# Ethylene_Sensor_Rev3.net
KiCad netlist of a schematic drawn in Altium Designer
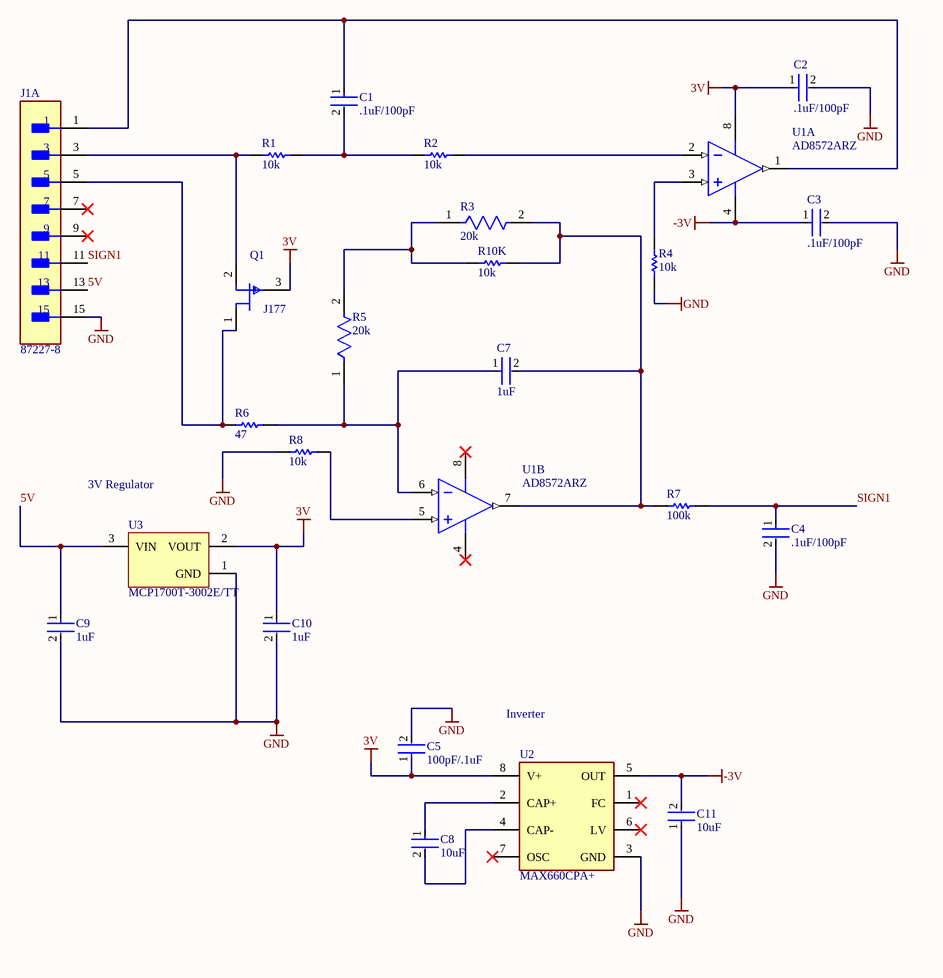
[diagram p0: Ethylene Sensor Rev3.SchDoc]

(export (version "E")
  (design (tool "Eeschema 10.0.6"))
  (components
    (comp (ref "C1")
      (value ".1uF/100pF")
      (footprint "FP-RCE0K1-MFG")
      (description "Cap Ceramic 100pF 100V C0G ±5% Radial 5mm +125°C Automotive Bulk")
      (fields (field (name "TOLERANCE") "5%"))
      (libsource (lib "Altium Content Vault") (part "b4654b650e69147ec39a6b967a45e02"))
    )
    (comp (ref "C2")
      (value ".1uF/100pF")
      (footprint "FP-RCE0K1-MFG")
      (description "Cap Ceramic 100pF 100V C0G ±5% Radial 5mm +125°C Automotive Bulk")
      (fields (field (name "TOLERANCE") "5%"))
      (libsource (lib "Altium Content Vault") (part "b4654b650e69147ec39a6b967a45e02"))
    )
    (comp (ref "C3")
      (value ".1uF/100pF")
      (footprint "FP-RCE0K1-MFG")
      (description "Cap Ceramic 100pF 100V C0G ±5% Radial 5mm +125°C Automotive Bulk")
      (fields (field (name "TOLERANCE") "5%"))
      (libsource (lib "Altium Content Vault") (part "b4654b650e69147ec39a6b967a45e02"))
    )
    (comp (ref "C4")
      (value ".1uF/100pF")
      (footprint "FP-RCE0K1-MFG")
      (description "Cap Ceramic 100pF 100V C0G ±5% Radial 5mm +125°C Automotive Bulk")
      (fields (field (name "TOLERANCE") "5%"))
      (libsource (lib "Altium Content Vault") (part "b4654b650e69147ec39a6b967a45e02"))
    )
    (comp (ref "C5")
      (value "100pF/.1uF")
      (footprint "FP-RCE0DB-MFG")
      (description "Cap Ceramic 100pF 100V C0G ±5% Radial 2.5mm +125°C Ammo Pack")
      (fields (field (name "TOLERANCE") "5%"))
      (libsource (lib "Altium Content Vault") (part "b4654b650e69147ec39a6b967a45e02"))
    )
    (comp (ref "C7")
      (value "1uF")
      (footprint "FP-K105Z20Y5VF5TL2-MFG")
      (description "CAP CER 1UF 50V Y5V RADIAL")
      (fields
        (field (name "TOLERANCE") "-20+80%")
        (field (name "OCTOPART") "https://octopart.com/k105z20y5vf5tl2-vishay-39475252")
      )
      (libsource (lib "Altium Content Vault") (part "11868f565c42a9108669ba33697ecf6"))
    )
    (comp (ref "C8")
      (value "10uF")
      (footprint "FP-RCE3M1-MFG")
      (description "Cap Ceramic 10uF 25V X7R ±10% Radial 5mm +125°C Automotive Ammo Pack")
      (fields (field (name "TOLERANCE") "10%"))
      (libsource (lib "Altium Content Vault") (part "02cd4be3c70576c341d710602a673aa"))
    )
    (comp (ref "C9")
      (value "1uF")
      (footprint "FP-K105Z20Y5VF5TL2-MFG")
      (description "CAP CER 1UF 50V Y5V RADIAL")
      (fields
        (field (name "TOLERANCE") "-20+80%")
        (field (name "OCTOPART") "https://octopart.com/k105z20y5vf5tl2-vishay-39475252")
      )
      (libsource (lib "Altium Content Vault") (part "11868f565c42a9108669ba33697ecf6"))
    )
    (comp (ref "C10")
      (value "1uF")
      (footprint "FP-K105Z20Y5VF5TL2-MFG")
      (description "CAP CER 1UF 50V Y5V RADIAL")
      (fields
        (field (name "TOLERANCE") "-20+80%")
        (field (name "OCTOPART") "https://octopart.com/k105z20y5vf5tl2-vishay-39475252")
      )
      (libsource (lib "Altium Content Vault") (part "11868f565c42a9108669ba33697ecf6"))
    )
    (comp (ref "C11")
      (value "10uF")
      (footprint "FP-RCE3M1-MFG")
      (description "Cap Ceramic 10uF 25V X7R ±10% Radial 5mm +125°C Automotive Ammo Pack")
      (fields (field (name "TOLERANCE") "10%"))
      (libsource (lib "Altium Content Vault") (part "02cd4be3c70576c341d710602a673aa"))
    )
    (comp (ref "J1")
      (value "87227-8")
      (footprint "FP-87227-8-MFG")
      (description "CONN HEADER VERT 16POS 2.54MM")
      (fields
        (field (name "MANUFACTURER") "TE Connectivity")
        (field (name "OCTOPART") "https://octopart.com/87227-8-te+connectivity-39407754")
      )
      (libsource (lib "Altium Content Vault") (part "4b6d22b45e2f925f038cba5d936fbcc"))
    )
    (comp (ref "Q1")
      (value "J177")
      (footprint "FP-318-08-IPC_C")
      (description "JFET P-CH 30V 0.225W SOT23")
      (libsource (lib "Altium Content Vault") (part "f35b6042eff1b6cb0a0a26375b7670e"))
    )
    (comp (ref "R1")
      (value "10k")
      (footprint "OMTE-RES7X2.5-2")
      (fields
        (field (name "TOLERANCE") "±5%")
        (field (name "PARTNUMBER") "OD103JE")
        (field (name "MANUFACTURER") "Ohmite")
      )
      (libsource (lib "Altium Content Vault") (part "RES-2"))
    )
    (comp (ref "R2")
      (value "10k")
      (footprint "OMTE-RES7X2.5-2")
      (fields
        (field (name "TOLERANCE") "±5%")
        (field (name "PARTNUMBER") "OD103JE")
        (field (name "MANUFACTURER") "Ohmite")
      )
      (libsource (lib "Altium Content Vault") (part "RES-2"))
    )
    (comp (ref "R3")
      (value "20k")
      (footprint "FP-S102K-MFG")
      (description "RES 20K OHM 0.6W 0.01% RADIAL")
      (fields (field (name "TOLERANCE") "0.01%"))
      (libsource (lib "Altium Content Vault") (part "1029c3af85768c4190bb7ad29bc67b5"))
    )
    (comp (ref "R4")
      (value "10k")
      (footprint "OMTE-RES7X2.5-2")
      (fields
        (field (name "TOLERANCE") "±5%")
        (field (name "PARTNUMBER") "OD103JE")
        (field (name "MANUFACTURER") "Ohmite")
      )
      (libsource (lib "Altium Content Vault") (part "RES-2"))
    )
    (comp (ref "R5")
      (value "20k")
      (footprint "FP-S102K-MFG")
      (description "RES 20K OHM 0.6W 0.01% RADIAL")
      (fields (field (name "TOLERANCE") "0.01%"))
      (libsource (lib "Altium Content Vault") (part "1029c3af85768c4190bb7ad29bc67b5"))
    )
    (comp (ref "R6")
      (value "47")
      (footprint "RESC1609X50X30LL10T20")
      (fields (field (name "MANUFACTURER") "Vishay Dale") (field (name "PART NUMBER") "CRCW060347R0FKEA"))
      (libsource (lib "Altium Content Vault") (part "RES"))
    )
    (comp (ref "R7")
      (value "100k")
      (footprint "RESA60-630X240")
      (description "Axial Resistor, 100 KOhm, +/- 1%, 0.25 W, -55 to 155 degC, 2-Pin THD, RoHS, Bulk")
      (fields (field (name "TOLERANCE") "1%"))
      (libsource (lib "Altium Content Vault") (part "RES-2"))
    )
    (comp (ref "R8")
      (value "10k")
      (footprint "OMTE-RES7X2.5-2")
      (fields
        (field (name "TOLERANCE") "±5%")
        (field (name "PARTNUMBER") "OD103JE")
        (field (name "MANUFACTURER") "Ohmite")
      )
      (libsource (lib "Altium Content Vault") (part "RES-2"))
    )
    (comp (ref "R10K")
      (value "10k")
      (footprint "OMTE-RES7X2.5-2")
      (fields
        (field (name "TOLERANCE") "±5%")
        (field (name "PARTNUMBER") "OD103JE")
        (field (name "MANUFACTURER") "Ohmite")
      )
      (libsource (lib "Altium Content Vault") (part "RES-2"))
    )
    (comp (ref "U1")
      (value "AD8572ARZ")
      (footprint "ADI-R-8_L")
      (fields (field (name "MANUFACTURER") "Analog Devices") (field (name "GENERIC PART NUMBER") "AD8572"))
      (libsource (lib "Altium Content Vault") (part "ADI-OP29X-R-8"))
    )
    (comp (ref "U2")
      (value "MAX660CPA+")
      (footprint "FP-P8-2-MFG")
      (description "IC REG CHARG PUMP INV 100MA 8DIP")
      (fields
        (field (name "OCTOPART") "https://octopart.com/max660cpa%2B-maxim+integrated-39427913")
        (field (name "MANUFACTURER") "Maxim Integrated")
      )
      (libsource (lib "Altium Content Vault") (part "cb4f88f8f8861f0afe4fdc40404f196"))
    )
    (comp (ref "U3")
      (value "MCP1700T-3002E/TT")
      (footprint "SOT-23-TT3_L")
      (description "Low Quiescent Current LDO, 3-Pin SOT-23, Extended Temperature, Tape and Reel")
      (libsource (lib "Altium Content Vault") (part "PM-LINEREG-MCP1700-IL3"))
    )
  )
  (nets
    (net (code "1") (name "-3V") (class "Default")
      (node (ref "C11") (pin "2") (pinfunction "2_2") (pintype "passive"))
      (node (ref "C3") (pin "1") (pinfunction "1_1") (pintype "passive"))
      (node (ref "U1") (pin "4") (pinfunction "-V_4") (pintype "power_in"))
      (node (ref "U2") (pin "5") (pinfunction "OUT_5") (pintype "power_in"))
    )
    (net (code "2") (name "/5V") (class "Default")
      (node (ref "C9") (pin "1") (pinfunction "1_1") (pintype "passive"))
      (node (ref "J1") (pin "13") (pinfunction "13_13") (pintype "passive"))
      (node (ref "U3") (pin "3") (pinfunction "VIN_3") (pintype "power_in"))
    )
    (net (code "3") (name "/SIGN1") (class "Default")
      (node (ref "C4") (pin "1") (pinfunction "1_1") (pintype "passive"))
      (node (ref "J1") (pin "11") (pinfunction "11_11") (pintype "passive"))
      (node (ref "R7") (pin "2") (pinfunction "2_2") (pintype "passive"))
    )
    (net (code "4") (name "3V") (class "Default")
      (node (ref "C10") (pin "1") (pinfunction "1_1") (pintype "passive"))
      (node (ref "C2") (pin "1") (pinfunction "1_1") (pintype "passive"))
      (node (ref "C5") (pin "1") (pinfunction "1_1") (pintype "passive"))
      (node (ref "Q1") (pin "3") (pinfunction "G_3") (pintype "passive"))
      (node (ref "U1") (pin "8") (pinfunction "+V_8") (pintype "power_in"))
      (node (ref "U2") (pin "8") (pinfunction "V+_8") (pintype "power_in"))
      (node (ref "U3") (pin "2") (pinfunction "VOUT_2") (pintype "power_in"))
    )
    (net (code "5") (name "GND") (class "Default")
      (node (ref "C10") (pin "2") (pinfunction "2_2") (pintype "passive"))
      (node (ref "C11") (pin "1") (pinfunction "1_1") (pintype "passive"))
      (node (ref "C2") (pin "2") (pinfunction "2_2") (pintype "passive"))
      (node (ref "C3") (pin "2") (pinfunction "2_2") (pintype "passive"))
      (node (ref "C4") (pin "2") (pinfunction "2_2") (pintype "passive"))
      (node (ref "C5") (pin "2") (pinfunction "2_2") (pintype "passive"))
      (node (ref "C9") (pin "2") (pinfunction "2_2") (pintype "passive"))
      (node (ref "J1") (pin "15") (pinfunction "15_15") (pintype "passive"))
      (node (ref "R4") (pin "1") (pinfunction "1_1") (pintype "passive"))
      (node (ref "R8") (pin "1") (pinfunction "1_1") (pintype "passive"))
      (node (ref "U2") (pin "3") (pinfunction "GND_3") (pintype "power_in"))
      (node (ref "U3") (pin "1") (pinfunction "GND_1") (pintype "power_in"))
    )
    (net (code "6") (name "Net-(C1-Pad2)") (class "Default")
      (node (ref "C1") (pin "2") (pinfunction "2_2") (pintype "passive"))
      (node (ref "R1") (pin "2") (pinfunction "2_2") (pintype "passive"))
      (node (ref "R2") (pin "1") (pinfunction "1_1") (pintype "passive"))
    )
    (net (code "7") (name "Net-(Q1-D)") (class "Default")
      (node (ref "J1") (pin "5") (pinfunction "5_5") (pintype "passive"))
      (node (ref "Q1") (pin "1") (pinfunction "D_1") (pintype "passive"))
      (node (ref "R6") (pin "1") (pinfunction "1_1") (pintype "passive"))
    )
    (net (code "8") (name "Net-(Q1-S)") (class "Default")
      (node (ref "J1") (pin "3") (pinfunction "3_3") (pintype "passive"))
      (node (ref "Q1") (pin "2") (pinfunction "S_2") (pintype "passive"))
      (node (ref "R1") (pin "1") (pinfunction "1_1") (pintype "passive"))
    )
    (net (code "9") (name "Net-(R10K-Pad1)") (class "Default")
      (node (ref "R10K") (pin "1") (pinfunction "1_1") (pintype "passive"))
      (node (ref "R3") (pin "1") (pinfunction "1_1") (pintype "passive"))
      (node (ref "R5") (pin "2") (pinfunction "2_2") (pintype "passive"))
    )
    (net (code "10") (name "Net-(U1A-+IN_A)") (class "Default")
      (node (ref "R4") (pin "2") (pinfunction "2_2") (pintype "passive"))
      (node (ref "U1") (pin "3") (pinfunction "+IN_A_3") (pintype "input"))
    )
    (net (code "11") (name "Net-(U1A--IN_A)") (class "Default")
      (node (ref "R2") (pin "2") (pinfunction "2_2") (pintype "passive"))
      (node (ref "U1") (pin "2") (pinfunction "-IN_A_2") (pintype "input"))
    )
    (net (code "12") (name "Net-(U1A-OUT_A)") (class "Default")
      (node (ref "C1") (pin "1") (pinfunction "1_1") (pintype "passive"))
      (node (ref "J1") (pin "1") (pinfunction "1_1") (pintype "passive"))
      (node (ref "U1") (pin "1") (pinfunction "OUT_A_1") (pintype "output"))
    )
    (net (code "13") (name "Net-(U1B-+IN_B)") (class "Default")
      (node (ref "R8") (pin "2") (pinfunction "2_2") (pintype "passive"))
      (node (ref "U1") (pin "5") (pinfunction "+IN_B_5") (pintype "input"))
    )
    (net (code "14") (name "Net-(U1B--IN_B)") (class "Default")
      (node (ref "C7") (pin "1") (pinfunction "1_1") (pintype "passive"))
      (node (ref "R5") (pin "1") (pinfunction "1_1") (pintype "passive"))
      (node (ref "R6") (pin "2") (pinfunction "2_2") (pintype "passive"))
      (node (ref "U1") (pin "6") (pinfunction "-IN_B_6") (pintype "input"))
    )
    (net (code "15") (name "Net-(U1B-OUT_B)") (class "Default")
      (node (ref "C7") (pin "2") (pinfunction "2_2") (pintype "passive"))
      (node (ref "R10K") (pin "2") (pinfunction "2_2") (pintype "passive"))
      (node (ref "R3") (pin "2") (pinfunction "2_2") (pintype "passive"))
      (node (ref "R7") (pin "1") (pinfunction "1_1") (pintype "passive"))
      (node (ref "U1") (pin "7") (pinfunction "OUT_B_7") (pintype "output"))
    )
    (net (code "16") (name "Net-(U2-CAP+)") (class "Default")
      (node (ref "C8") (pin "1") (pinfunction "1_1") (pintype "passive"))
      (node (ref "U2") (pin "2") (pinfunction "CAP+_2") (pintype "passive"))
    )
    (net (code "17") (name "Net-(U2-CAP-)") (class "Default")
      (node (ref "C8") (pin "2") (pinfunction "2_2") (pintype "passive"))
      (node (ref "U2") (pin "4") (pinfunction "CAP-_4") (pintype "passive"))
    )
    (net (code "18") (name "unconnected-(J1-Pad7)") (class "Default")
      (node (ref "J1") (pin "7") (pinfunction "7_7") (pintype "passive+no_connect"))
    )
    (net (code "19") (name "unconnected-(J1-Pad9)") (class "Default")
      (node (ref "J1") (pin "9") (pinfunction "9_9") (pintype "passive+no_connect"))
    )
    (net (code "20") (name "unconnected-(U1B-+V-Pad8)") (class "Default")
      (node (ref "U1") (pin "8") (pinfunction "+V_8") (pintype "power_in+no_connect"))
    )
    (net (code "21") (name "unconnected-(U1B--V-Pad4)") (class "Default")
      (node (ref "U1") (pin "4") (pinfunction "-V_4") (pintype "power_in+no_connect"))
    )
    (net (code "22") (name "unconnected-(U2-FC-Pad1)") (class "Default")
      (node (ref "U2") (pin "1") (pinfunction "FC_1") (pintype "passive+no_connect"))
    )
    (net (code "23") (name "unconnected-(U2-LV-Pad6)") (class "Default")
      (node (ref "U2") (pin "6") (pinfunction "LV_6") (pintype "passive+no_connect"))
    )
    (net (code "24") (name "unconnected-(U2-OSC-Pad7)") (class "Default")
      (node (ref "U2") (pin "7") (pinfunction "OSC_7") (pintype "passive+no_connect"))
    )
  )
)
